# ForceSensor.net
KiCad netlist of a schematic drawn in EAGLE
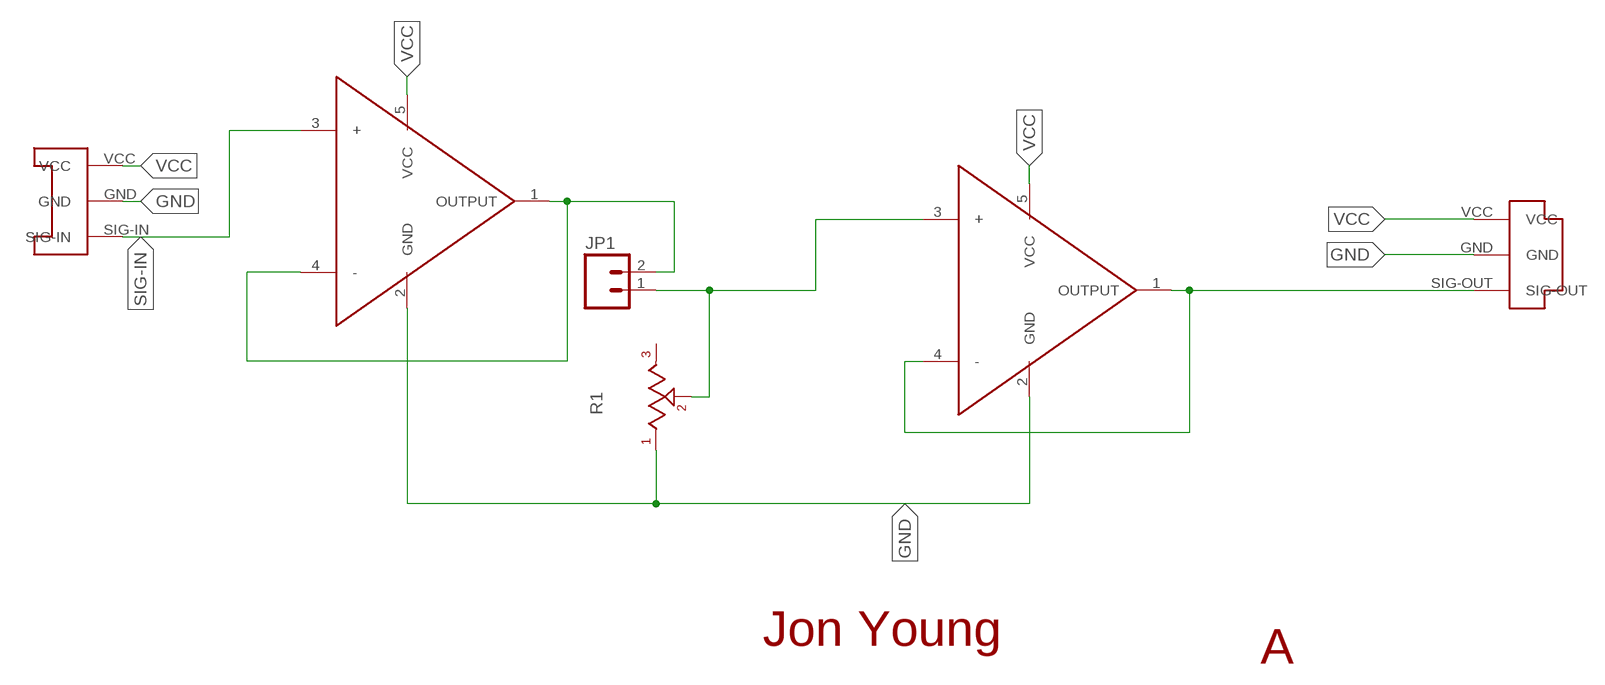
[diagram p0: schematic, sheet 1]

(export (version "E")
  (design (tool "Eeschema 10.0.6"))
  (components
    (comp (ref "JP1")
      (value "M02PTH3")
      (footprint "eagle-import:1X02_LONGPADS")
      (libsource (lib "eagle-import") (part "M02PTH3"))
    )
    (comp (ref "R1")
      (value "POT-TRIM-SMD-BOURNS-3314J-1")
      (footprint "eagle-import:POT-TRIM-SMD-BOURNS-3314")
      (libsource (lib "eagle-import") (part "POT-TRIM-SMD-BOURNS-3314J-1"))
    )
    (comp (ref "U$1")
      (value "CONN-PLUG-3POS-3MM")
      (footprint "eagle-import:PLUG-3POS-3MM-SMD")
      (libsource (lib "eagle-import") (part "CONN-PLUG-3POS-3MM"))
    )
    (comp (ref "U$2")
      (value "CONN-SOCKET-3POS-3MM")
      (footprint "eagle-import:SOCKET-3POS-3MM-SMD")
      (libsource (lib "eagle-import") (part "CONN-SOCKET-3POS-3MM"))
    )
    (comp (ref "U$3")
      (value "OPAMP-MCP6001SOT23-5")
      (footprint "eagle-import:SOT23-5")
      (libsource (lib "eagle-import") (part "OPAMP-MCP6001SOT23-5"))
    )
    (comp (ref "U$4")
      (value "OPAMP-MCP6001SOT23-5")
      (footprint "eagle-import:SOT23-5")
      (libsource (lib "eagle-import") (part "OPAMP-MCP6001SOT23-5"))
    )
  )
  (nets
    (net (code "1") (name "GND") (class "Default")
      (node (ref "R1") (pin "3") (pinfunction "1_3") (pintype "passive"))
      (node (ref "U$1") (pin "GND") (pinfunction "GND_GND") (pintype "power_in"))
      (node (ref "U$2") (pin "GND") (pinfunction "GND_GND") (pintype "power_in"))
      (node (ref "U$3") (pin "2") (pinfunction "GND_2") (pintype "power_in"))
      (node (ref "U$4") (pin "2") (pinfunction "GND_2") (pintype "power_in"))
    )
    (net (code "2") (name "Net-(U$3--)") (class "Default")
      (node (ref "JP1") (pin "2") (pinfunction "2_2") (pintype "passive"))
      (node (ref "U$3") (pin "1") (pinfunction "OUTPUT_1") (pintype "output"))
      (node (ref "U$3") (pin "4") (pinfunction "-_4") (pintype "input"))
    )
    (net (code "3") (name "Net-(U$4-+)") (class "Default")
      (node (ref "JP1") (pin "1") (pinfunction "1_1") (pintype "passive"))
      (node (ref "R1") (pin "2") (pinfunction "2_2") (pintype "passive"))
      (node (ref "U$4") (pin "3") (pinfunction "+_3") (pintype "input"))
    )
    (net (code "4") (name "Net-(U$4--)") (class "Default")
      (node (ref "U$1") (pin "SIG-OUT") (pinfunction "SIG-OUT_SIG-OUT") (pintype "bidirectional"))
      (node (ref "U$4") (pin "1") (pinfunction "OUTPUT_1") (pintype "output"))
      (node (ref "U$4") (pin "4") (pinfunction "-_4") (pintype "input"))
    )
    (net (code "5") (name "SIG-IN") (class "Default")
      (node (ref "U$2") (pin "SIG-IN") (pinfunction "SIG-IN_SIG-IN") (pintype "bidirectional"))
      (node (ref "U$3") (pin "3") (pinfunction "+_3") (pintype "input"))
    )
    (net (code "6") (name "VCC") (class "Default")
      (node (ref "U$1") (pin "VCC") (pinfunction "VCC_VCC") (pintype "power_in"))
      (node (ref "U$2") (pin "VCC") (pinfunction "VCC_VCC") (pintype "power_in"))
      (node (ref "U$3") (pin "5") (pinfunction "VCC_5") (pintype "power_in"))
      (node (ref "U$4") (pin "5") (pinfunction "VCC_5") (pintype "power_in"))
    )
    (net (code "7") (name "unconnected-(R1-3-Pad1)") (class "Default")
      (node (ref "R1") (pin "1") (pinfunction "3_1") (pintype "passive"))
    )
  )
)
